# msp430g2553.net
KiCad netlist of a schematic drawn in Altium Designer
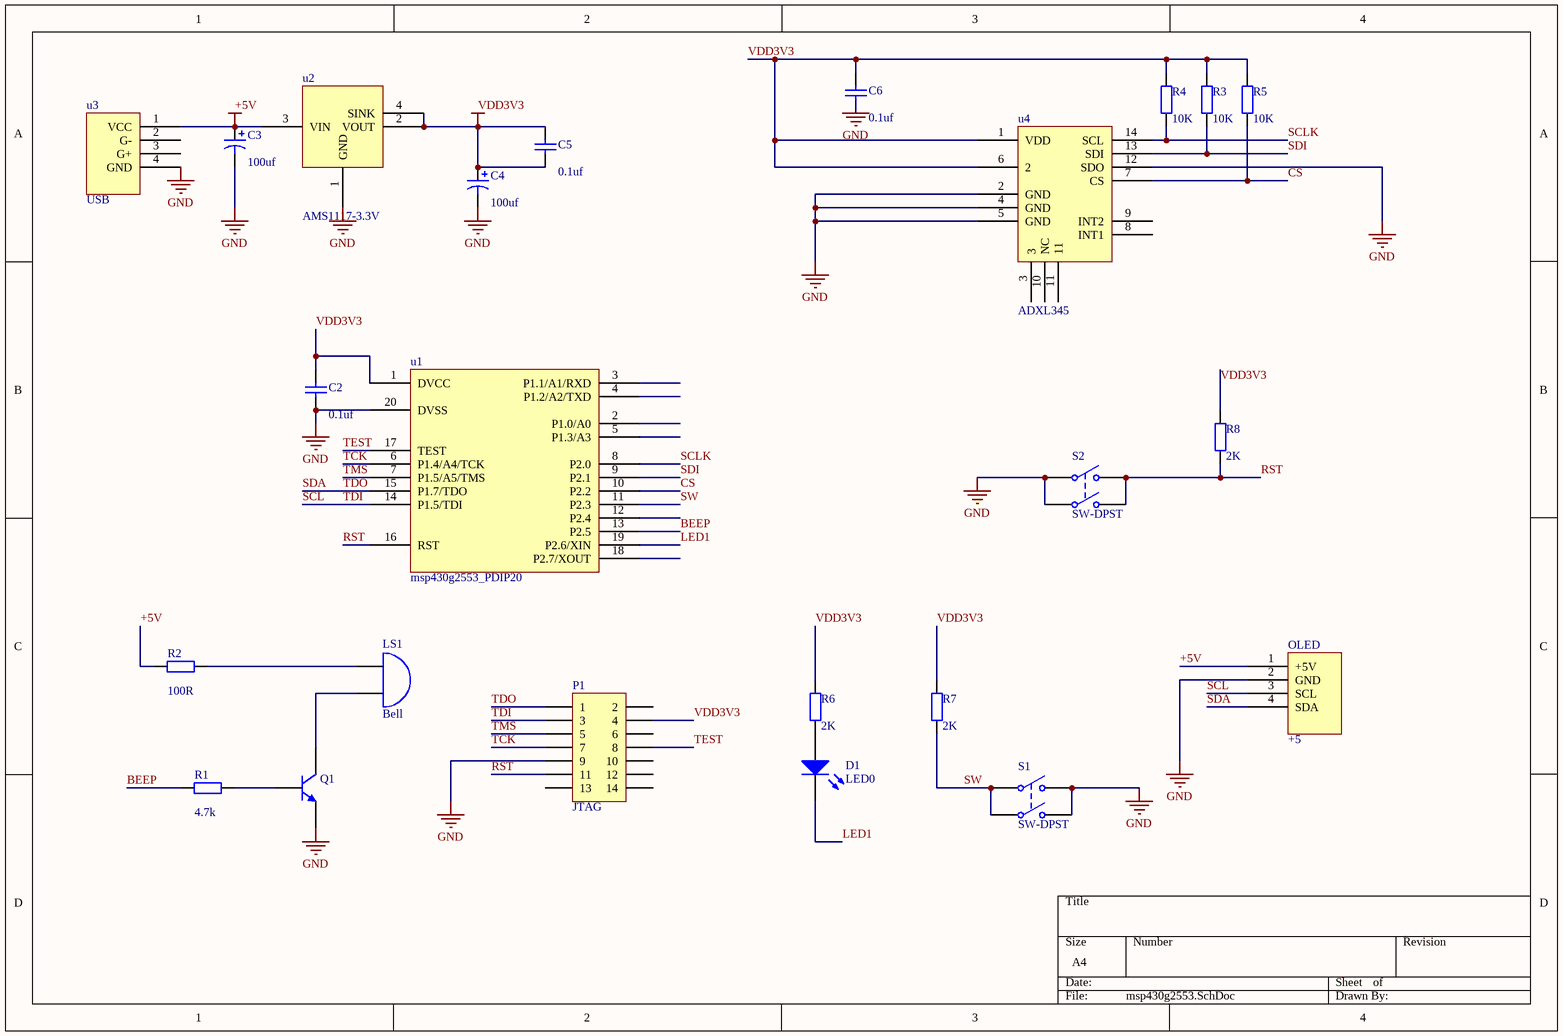
[diagram p0: msp430g2553.SchDoc]

(export (version "E")
  (design (tool "Eeschema 10.0.6"))
  (components
    (comp (ref "C2")
      (value "0.1uf")
      (footprint "6-0805_N")
      (description "Capacitor")
      (fields (field (name "Comment") "Cap") (field (name "PUBLISHER") "Altium Limited"))
      (libsource (lib "msp430g2553") (part "Cap"))
    )
    (comp (ref "C3")
      (value "100uf")
      (footprint "Cap2_polar")
      (description "Polarized Capacitor (Axial)")
      (fields (field (name "Comment") "Cap Pol2") (field (name "PUBLISHER") "Altium Limited"))
      (libsource (lib "msp430g2553") (part "Cap Pol2"))
    )
    (comp (ref "C4")
      (value "100uf")
      (footprint "Cap2_polar")
      (description "Polarized Capacitor (Axial)")
      (fields (field (name "Comment") "Cap Pol2") (field (name "PUBLISHER") "Altium Limited"))
      (libsource (lib "msp430g2553") (part "Cap Pol2"))
    )
    (comp (ref "C5")
      (value "0.1uf")
      (footprint "6-0805_N")
      (description "Capacitor")
      (fields (field (name "Comment") "Cap") (field (name "PUBLISHER") "Altium Limited"))
      (libsource (lib "msp430g2553") (part "Cap"))
    )
    (comp (ref "C6")
      (value "0.1uf")
      (footprint "6-0805_N")
      (description "Capacitor")
      (fields (field (name "Comment") "Cap") (field (name "PUBLISHER") "Altium Limited"))
      (libsource (lib "msp430g2553") (part "Cap"))
    )
    (comp (ref "D1")
      (value "LED0")
      (footprint "6-0805_N - duplicate")
      (description "Typical INFRARED GaAs LED")
      (fields (field (name "PUBLISHER") "Altium Limited"))
      (libsource (lib "msp430g2553") (part "LED0"))
    )
    (comp (ref "LS1")
      (value "Bell")
      (footprint "bell")
      (description "Electrical Bell")
      (fields (field (name "PUBLISHER") "Altium Limited"))
      (libsource (lib "msp430g2553") (part "Bell"))
    )
    (comp (ref "OLED") (value "+5") (footprint "OLED") (libsource (lib "msp430g2553") (part "OLED")))
    (comp (ref "P1")
      (value "JTAG")
      (footprint "HDR2X7H")
      (description "Header, 7-Pin, Dual row")
      (fields (field (name "PUBLISHER") "Altium Limited"))
      (libsource (lib "msp430g2553") (part "JTAG"))
    )
    (comp (ref "Q1")
      (value "NPN")
      (footprint "SOT23_N")
      (description "NPN Bipolar Transistor")
      (fields (field (name "PUBLISHER") "Altium Limited"))
      (libsource (lib "msp430g2553") (part "NPN"))
    )
    (comp (ref "R1")
      (value "4.7k")
      (footprint "6-0805_N")
      (description "Resistor")
      (fields (field (name "Comment") "Res2") (field (name "PUBLISHER") "Altium Limited"))
      (libsource (lib "") (part "Res2_1"))
    )
    (comp (ref "R2")
      (value "100R")
      (footprint "6-0805_N")
      (description "Resistor")
      (fields (field (name "Comment") "Res2") (field (name "PUBLISHER") "Altium Limited"))
      (libsource (lib "") (part "Res2_1"))
    )
    (comp (ref "R3")
      (value "10K")
      (footprint "6-0805_N")
      (description "Resistor")
      (fields (field (name "Comment") "Res2") (field (name "PUBLISHER") "Altium Limited"))
      (libsource (lib "msp430g2553") (part "Res2"))
    )
    (comp (ref "R4")
      (value "10K")
      (footprint "6-0805_N")
      (description "Resistor")
      (fields (field (name "Comment") "Res2") (field (name "PUBLISHER") "Altium Limited"))
      (libsource (lib "msp430g2553") (part "Res2"))
    )
    (comp (ref "R5")
      (value "10K")
      (footprint "6-0805_N")
      (description "Resistor")
      (fields (field (name "Comment") "Res2") (field (name "PUBLISHER") "Altium Limited"))
      (libsource (lib "msp430g2553") (part "Res2"))
    )
    (comp (ref "R6")
      (value "2K")
      (footprint "6-0805_N")
      (description "Resistor")
      (fields (field (name "Comment") "Res2") (field (name "PUBLISHER") "Altium Limited"))
      (libsource (lib "msp430g2553") (part "Res2"))
    )
    (comp (ref "R7")
      (value "2K")
      (footprint "6-0805_N")
      (description "Resistor")
      (fields (field (name "Comment") "Res2") (field (name "PUBLISHER") "Altium Limited"))
      (libsource (lib "msp430g2553") (part "Res2"))
    )
    (comp (ref "R8")
      (value "2K")
      (footprint "6-0805_N")
      (description "Resistor")
      (fields (field (name "Comment") "Res2") (field (name "PUBLISHER") "Altium Limited"))
      (libsource (lib "msp430g2553") (part "Res2"))
    )
    (comp (ref "S1")
      (value "SW-DPST")
      (footprint "DPST-4")
      (description "Double-Pole, Single-Throw Switch")
      (fields (field (name "PUBLISHER") "Altium Limited"))
      (libsource (lib "msp430g2553") (part "SW-DPST"))
    )
    (comp (ref "S2")
      (value "SW-DPST")
      (footprint "DPST-4")
      (description "Double-Pole, Single-Throw Switch")
      (fields (field (name "PUBLISHER") "Altium Limited"))
      (libsource (lib "msp430g2553") (part "SW-DPST"))
    )
    (comp (ref "u1")
      (value "msp430g2553_PDIP20")
      (footprint "DIP20")
      (libsource (lib "msp430g2553") (part "msp430g2553_PDIP20"))
    )
    (comp (ref "u2")
      (value "AMS1117-3.3V")
      (footprint "SOT223_N")
      (libsource (lib "msp430g2553") (part "AMS1117-3.3V"))
    )
    (comp (ref "u3") (value "USB") (footprint "USB2.5-2H4") (libsource (lib "msp430g2553") (part "USB")))
    (comp (ref "u4") (value "ADXL345") (footprint "ADXL345") (libsource (lib "msp430g2553") (part "ADXL345")))
  )
  (nets
    (net (code "1") (name "+5") (class "Default")
      (node (ref "C3") (pin "2") (pinfunction "2_2") (pintype "passive"))
      (node (ref "u2") (pin "3") (pinfunction "VIN_3") (pintype "passive"))
      (node (ref "u3") (pin "1") (pinfunction "VCC_1") (pintype "passive"))
    )
    (net (code "2") (name "/+5V") (class "Default")
      (node (ref "OLED") (pin "1") (pinfunction "+5V_1") (pintype "passive"))
      (node (ref "R2") (pin "1") (pinfunction "1_1") (pintype "passive"))
    )
    (net (code "3") (name "/BEEP") (class "Default")
      (node (ref "R1") (pin "1") (pinfunction "1_1") (pintype "passive"))
      (node (ref "u1") (pin "13") (pinfunction "P2.5_13") (pintype "passive"))
    )
    (net (code "4") (name "/CS") (class "Default")
      (node (ref "R5") (pin "1") (pinfunction "1_1") (pintype "passive"))
      (node (ref "u1") (pin "10") (pinfunction "P2.2_10") (pintype "passive"))
      (node (ref "u4") (pin "7") (pinfunction "CS_7") (pintype "passive"))
    )
    (net (code "5") (name "/LED1") (class "Default")
      (node (ref "D1") (pin "2") (pinfunction "K_2") (pintype "passive"))
      (node (ref "u1") (pin "19") (pinfunction "P2.6/XIN_19") (pintype "passive"))
    )
    (net (code "6") (name "/RST") (class "Default")
      (node (ref "P1") (pin "11") (pinfunction "11_11") (pintype "passive"))
      (node (ref "R8") (pin "1") (pinfunction "1_1") (pintype "passive"))
      (node (ref "S2") (pin "3") (pinfunction "NO1_3") (pintype "passive"))
      (node (ref "S2") (pin "4") (pinfunction "NO2_4") (pintype "passive"))
      (node (ref "u1") (pin "16") (pinfunction "RST_16") (pintype "passive"))
    )
    (net (code "7") (name "/SCL") (class "Default")
      (node (ref "OLED") (pin "3") (pinfunction "SCL_3") (pintype "passive"))
      (node (ref "P1") (pin "3") (pinfunction "3_3") (pintype "passive"))
      (node (ref "u1") (pin "14") (pinfunction "P1.5/TDI_14") (pintype "passive"))
    )
    (net (code "8") (name "/SCLK") (class "Default")
      (node (ref "R4") (pin "1") (pinfunction "1_1") (pintype "passive"))
      (node (ref "u1") (pin "8") (pinfunction "P2.0_8") (pintype "passive"))
      (node (ref "u4") (pin "14") (pinfunction "SCL_14") (pintype "passive"))
    )
    (net (code "9") (name "/SDA") (class "Default")
      (node (ref "OLED") (pin "4") (pinfunction "SDA_4") (pintype "passive"))
      (node (ref "P1") (pin "1") (pinfunction "1_1") (pintype "passive"))
      (node (ref "u1") (pin "15") (pinfunction "P1.7/TDO_15") (pintype "passive"))
    )
    (net (code "10") (name "/SDI") (class "Default")
      (node (ref "R3") (pin "1") (pinfunction "1_1") (pintype "passive"))
      (node (ref "u1") (pin "9") (pinfunction "P2.1_9") (pintype "passive"))
      (node (ref "u4") (pin "13") (pinfunction "SDI_13") (pintype "passive"))
    )
    (net (code "11") (name "/SW") (class "Default")
      (node (ref "R7") (pin "1") (pinfunction "1_1") (pintype "passive"))
      (node (ref "S1") (pin "1") (pinfunction "COMMON1_1") (pintype "passive"))
      (node (ref "S1") (pin "2") (pinfunction "COMMON2_2") (pintype "passive"))
      (node (ref "u1") (pin "11") (pinfunction "P2.3_11") (pintype "passive"))
    )
    (net (code "12") (name "/TCK") (class "Default")
      (node (ref "P1") (pin "7") (pinfunction "7_7") (pintype "passive"))
      (node (ref "u1") (pin "6") (pinfunction "P1.4/A4/TCK_6") (pintype "passive"))
    )
    (net (code "13") (name "/TEST") (class "Default")
      (node (ref "P1") (pin "8") (pinfunction "8_8") (pintype "passive"))
      (node (ref "u1") (pin "17") (pinfunction "TEST_17") (pintype "passive"))
    )
    (net (code "14") (name "/TMS") (class "Default")
      (node (ref "P1") (pin "5") (pinfunction "5_5") (pintype "passive"))
      (node (ref "u1") (pin "7") (pinfunction "P1.5/A5/TMS_7") (pintype "passive"))
    )
    (net (code "15") (name "/VDD3V3") (class "Default")
      (node (ref "C2") (pin "2") (pinfunction "2_2") (pintype "passive"))
      (node (ref "C6") (pin "2") (pinfunction "2_2") (pintype "passive"))
      (node (ref "P1") (pin "4") (pinfunction "4_4") (pintype "passive"))
      (node (ref "R3") (pin "2") (pinfunction "2_2") (pintype "passive"))
      (node (ref "R4") (pin "2") (pinfunction "2_2") (pintype "passive"))
      (node (ref "R5") (pin "2") (pinfunction "2_2") (pintype "passive"))
      (node (ref "R6") (pin "2") (pinfunction "2_2") (pintype "passive"))
      (node (ref "R7") (pin "2") (pinfunction "2_2") (pintype "passive"))
      (node (ref "R8") (pin "2") (pinfunction "2_2") (pintype "passive"))
      (node (ref "u1") (pin "1") (pinfunction "DVCC_1") (pintype "passive"))
      (node (ref "u4") (pin "1") (pinfunction "VDD_1") (pintype "passive"))
      (node (ref "u4") (pin "6") (pinfunction "2_6") (pintype "passive"))
    )
    (net (code "16") (name "3.3") (class "Default")
      (node (ref "C4") (pin "2") (pinfunction "2_2") (pintype "passive"))
      (node (ref "C5") (pin "1") (pinfunction "1_1") (pintype "passive"))
      (node (ref "C5") (pin "2") (pinfunction "2_2") (pintype "passive"))
      (node (ref "u2") (pin "2") (pinfunction "VOUT_2") (pintype "passive"))
      (node (ref "u2") (pin "4") (pinfunction "SINK_4") (pintype "passive"))
    )
    (net (code "17") (name "GND") (class "Default")
      (node (ref "C2") (pin "1") (pinfunction "1_1") (pintype "passive"))
      (node (ref "C3") (pin "1") (pinfunction "1_1") (pintype "passive"))
      (node (ref "C4") (pin "1") (pinfunction "1_1") (pintype "passive"))
      (node (ref "C6") (pin "1") (pinfunction "1_1") (pintype "passive"))
      (node (ref "OLED") (pin "2") (pinfunction "GND_2") (pintype "passive"))
      (node (ref "P1") (pin "9") (pinfunction "9_9") (pintype "passive"))
      (node (ref "Q1") (pin "3") (pinfunction "E_3") (pintype "passive"))
      (node (ref "S1") (pin "3") (pinfunction "NO1_3") (pintype "passive"))
      (node (ref "S1") (pin "4") (pinfunction "NO2_4") (pintype "passive"))
      (node (ref "S2") (pin "1") (pinfunction "COMMON1_1") (pintype "passive"))
      (node (ref "S2") (pin "2") (pinfunction "COMMON2_2") (pintype "passive"))
      (node (ref "u1") (pin "20") (pinfunction "DVSS_20") (pintype "passive"))
      (node (ref "u2") (pin "1") (pinfunction "GND_1") (pintype "passive"))
      (node (ref "u3") (pin "4") (pinfunction "GND_4") (pintype "passive"))
      (node (ref "u4") (pin "12") (pinfunction "SDO_12") (pintype "passive"))
      (node (ref "u4") (pin "2") (pinfunction "GND_2") (pintype "passive"))
      (node (ref "u4") (pin "4") (pinfunction "GND_4") (pintype "passive"))
      (node (ref "u4") (pin "5") (pinfunction "GND_5") (pintype "passive"))
    )
    (net (code "18") (name "Net-(D1-A)") (class "Default")
      (node (ref "D1") (pin "1") (pinfunction "A_1") (pintype "passive"))
      (node (ref "R6") (pin "1") (pinfunction "1_1") (pintype "passive"))
    )
    (net (code "19") (name "Net-(LS1-A)") (class "Default")
      (node (ref "LS1") (pin "1") (pinfunction "A_1") (pintype "passive"))
      (node (ref "R2") (pin "2") (pinfunction "2_2") (pintype "passive"))
    )
    (net (code "20") (name "Net-(LS1-B)") (class "Default")
      (node (ref "LS1") (pin "2") (pinfunction "B_2") (pintype "passive"))
      (node (ref "Q1") (pin "1") (pinfunction "C_1") (pintype "passive"))
    )
    (net (code "21") (name "Net-(Q1-B)") (class "Default")
      (node (ref "Q1") (pin "2") (pinfunction "B_2") (pintype "passive"))
      (node (ref "R1") (pin "2") (pinfunction "2_2") (pintype "passive"))
    )
    (net (code "22") (name "unconnected-(P1-Pad2)") (class "Default")
      (node (ref "P1") (pin "2") (pinfunction "2_2") (pintype "passive"))
    )
    (net (code "23") (name "unconnected-(P1-Pad6)") (class "Default")
      (node (ref "P1") (pin "6") (pinfunction "6_6") (pintype "passive"))
    )
    (net (code "24") (name "unconnected-(P1-Pad10)") (class "Default")
      (node (ref "P1") (pin "10") (pinfunction "10_10") (pintype "passive"))
    )
    (net (code "25") (name "unconnected-(P1-Pad12)") (class "Default")
      (node (ref "P1") (pin "12") (pinfunction "12_12") (pintype "passive"))
    )
    (net (code "26") (name "unconnected-(P1-Pad13)") (class "Default")
      (node (ref "P1") (pin "13") (pinfunction "13_13") (pintype "passive"))
    )
    (net (code "27") (name "unconnected-(P1-Pad14)") (class "Default")
      (node (ref "P1") (pin "14") (pinfunction "14_14") (pintype "passive"))
    )
    (net (code "28") (name "unconnected-(u1-P1.0{slash}A0-Pad2)") (class "Default")
      (node (ref "u1") (pin "2") (pinfunction "P1.0/A0_2") (pintype "passive"))
    )
    (net (code "29") (name "unconnected-(u1-P1.1{slash}A1{slash}RXD-Pad3)") (class "Default")
      (node (ref "u1") (pin "3") (pinfunction "P1.1/A1/RXD_3") (pintype "passive"))
    )
    (net (code "30") (name "unconnected-(u1-P1.2{slash}A2{slash}TXD-Pad4)") (class "Default")
      (node (ref "u1") (pin "4") (pinfunction "P1.2/A2/TXD_4") (pintype "passive"))
    )
    (net (code "31") (name "unconnected-(u1-P1.3{slash}A3-Pad5)") (class "Default")
      (node (ref "u1") (pin "5") (pinfunction "P1.3/A3_5") (pintype "passive"))
    )
    (net (code "32") (name "unconnected-(u1-P2.4-Pad12)") (class "Default")
      (node (ref "u1") (pin "12") (pinfunction "P2.4_12") (pintype "passive"))
    )
    (net (code "33") (name "unconnected-(u1-P2.7{slash}XOUT-Pad18)") (class "Default")
      (node (ref "u1") (pin "18") (pinfunction "P2.7/XOUT_18") (pintype "passive"))
    )
    (net (code "34") (name "unconnected-(u3-G+-Pad3)") (class "Default")
      (node (ref "u3") (pin "3") (pinfunction "G+_3") (pintype "passive"))
    )
    (net (code "35") (name "unconnected-(u3-G--Pad2)") (class "Default")
      (node (ref "u3") (pin "2") (pinfunction "G-_2") (pintype "passive"))
    )
    (net (code "36") (name "unconnected-(u4-INT1-Pad8)") (class "Default")
      (node (ref "u4") (pin "8") (pinfunction "INT1_8") (pintype "passive"))
    )
    (net (code "37") (name "unconnected-(u4-INT2-Pad9)") (class "Default")
      (node (ref "u4") (pin "9") (pinfunction "INT2_9") (pintype "passive"))
    )
    (net (code "38") (name "unconnected-(u4-NC-Pad10)") (class "Default")
      (node (ref "u4") (pin "10") (pinfunction "NC_10") (pintype "passive"))
    )
    (net (code "39") (name "unconnected-(u4-Pad3)") (class "Default")
      (node (ref "u4") (pin "3") (pinfunction "3_3") (pintype "passive"))
    )
    (net (code "40") (name "unconnected-(u4-Pad11)") (class "Default")
      (node (ref "u4") (pin "11") (pinfunction "11_11") (pintype "passive"))
    )
  )
)
